# Uno_Base_Shield.net
KiCad netlist of a schematic drawn in EAGLE
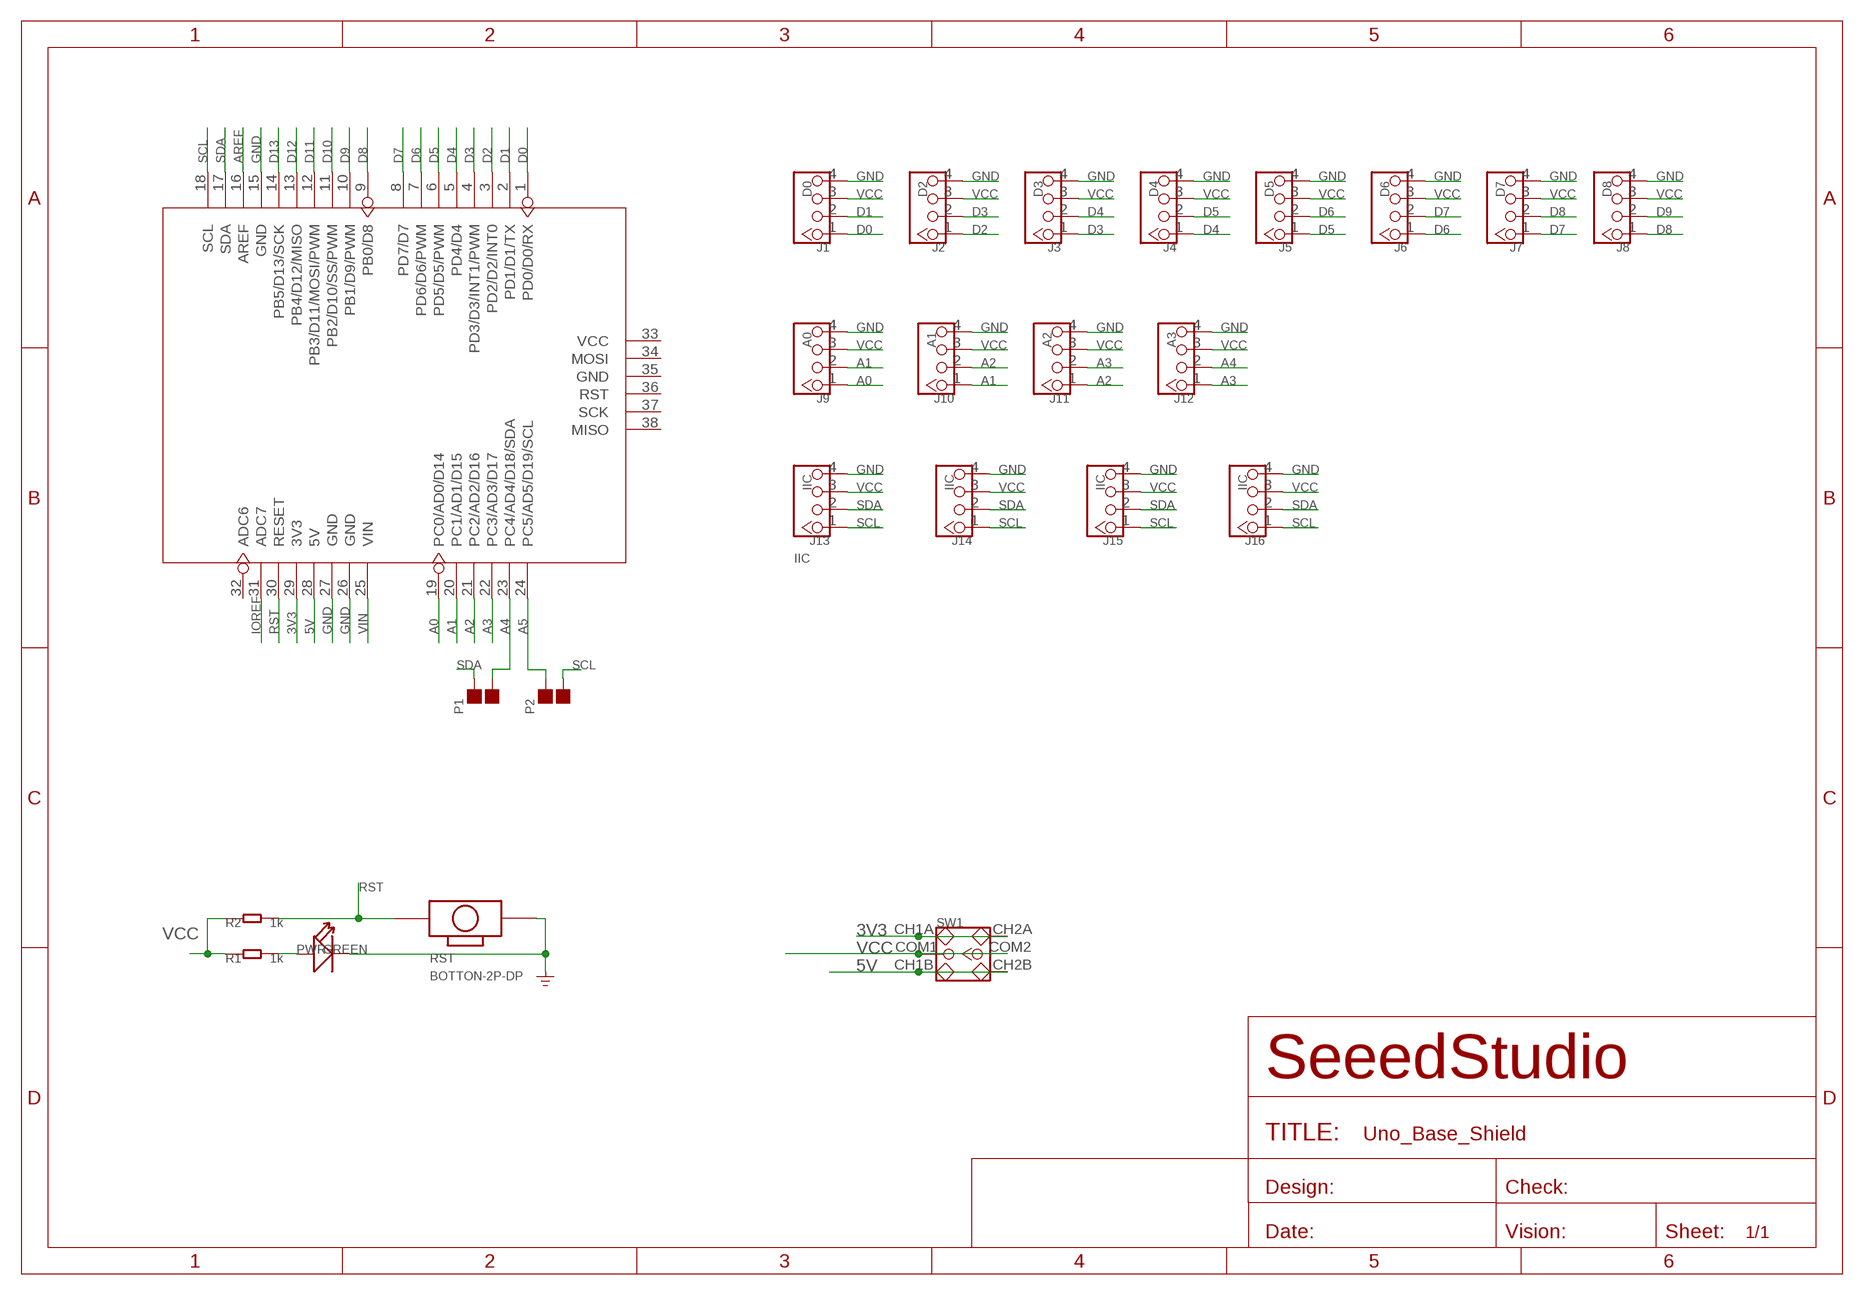
[diagram p0: schematic, sheet 1]

(export (version "E")
  (design (tool "Eeschema 10.0.6"))
  (components
    (comp (ref "J1")
      (value "D0")
      (footprint "eagle-import:4P-2.0")
      (libsource (lib "eagle-import") (part "TWIG-4P-2.0-2.0"))
    )
    (comp (ref "J2")
      (value "D2")
      (footprint "eagle-import:4P-2.0")
      (libsource (lib "eagle-import") (part "TWIG-4P-2.0-2.0"))
    )
    (comp (ref "J3")
      (value "D3")
      (footprint "eagle-import:4P-2.0")
      (libsource (lib "eagle-import") (part "TWIG-4P-2.0-2.0"))
    )
    (comp (ref "J4")
      (value "D4")
      (footprint "eagle-import:4P-2.0")
      (libsource (lib "eagle-import") (part "TWIG-4P-2.0-2.0"))
    )
    (comp (ref "J5")
      (value "D5")
      (footprint "eagle-import:4P-2.0")
      (libsource (lib "eagle-import") (part "TWIG-4P-2.0-2.0"))
    )
    (comp (ref "J6")
      (value "D6")
      (footprint "eagle-import:4P-2.0")
      (libsource (lib "eagle-import") (part "TWIG-4P-2.0-2.0"))
    )
    (comp (ref "J7")
      (value "D7")
      (footprint "eagle-import:4P-2.0")
      (libsource (lib "eagle-import") (part "TWIG-4P-2.0-2.0"))
    )
    (comp (ref "J8")
      (value "D8")
      (footprint "eagle-import:4P-2.0")
      (libsource (lib "eagle-import") (part "TWIG-4P-2.0-2.0"))
    )
    (comp (ref "J9")
      (value "A0")
      (footprint "eagle-import:4P-2.0-90D")
      (libsource (lib "eagle-import") (part "TWIG-4P-2.0'90D'"))
    )
    (comp (ref "J10")
      (value "A1")
      (footprint "eagle-import:4P-2.0-90D")
      (libsource (lib "eagle-import") (part "TWIG-4P-2.0'90D'"))
    )
    (comp (ref "J11")
      (value "A2")
      (footprint "eagle-import:4P-2.0-90D")
      (libsource (lib "eagle-import") (part "TWIG-4P-2.0'90D'"))
    )
    (comp (ref "J12")
      (value "A3")
      (footprint "eagle-import:4P-2.0-90D")
      (libsource (lib "eagle-import") (part "TWIG-4P-2.0'90D'"))
    )
    (comp (ref "J13")
      (value "IIC")
      (footprint "eagle-import:4P-2.0")
      (libsource (lib "eagle-import") (part "TWIG-4P-2.0-2.0"))
    )
    (comp (ref "J14")
      (value "IIC")
      (footprint "eagle-import:4P-2.0")
      (libsource (lib "eagle-import") (part "TWIG-4P-2.0-2.0"))
    )
    (comp (ref "J15")
      (value "IIC")
      (footprint "eagle-import:4P-2.0")
      (libsource (lib "eagle-import") (part "TWIG-4P-2.0-2.0"))
    )
    (comp (ref "J16")
      (value "IIC")
      (footprint "eagle-import:4P-2.0")
      (libsource (lib "eagle-import") (part "TWIG-4P-2.0-2.0"))
    )
    (comp (ref "P1")
      (value "DNP")
      (footprint "eagle-import:2P-SMD-1.78X1.27")
      (libsource (lib "eagle-import") (part "PAD-JUMPER-2P"))
    )
    (comp (ref "P2")
      (value "DNP")
      (footprint "eagle-import:2P-SMD-1.78X1.27")
      (libsource (lib "eagle-import") (part "PAD-JUMPER-2P"))
    )
    (comp (ref "PWR")
      (value "GREEN")
      (footprint "eagle-import:LED-2P-2.54-3MM")
      (libsource (lib "eagle-import") (part "LED-3MM"))
    )
    (comp (ref "R1")
      (value "1k")
      (footprint "eagle-import:R0603")
      (libsource (lib "eagle-import") (part "R-0603"))
    )
    (comp (ref "R2")
      (value "1k")
      (footprint "eagle-import:R0603")
      (libsource (lib "eagle-import") (part "R-0603"))
    )
    (comp (ref "RST")
      (value "BOTTON-2P-DP")
      (footprint "eagle-import:2P-7.62X3.56-90D")
      (libsource (lib "eagle-import") (part "BOTTON-2P-90"))
    )
    (comp (ref "SW1")
      (value "SWITCH-2CH-6P'90D'")
      (footprint "eagle-import:6P-2CH-2.5-9.1X3.5X3.2H-90D")
      (libsource (lib "eagle-import") (part "SWITCH-2CH-6P'90D'"))
    )
    (comp (ref "U2")
      (value "DIP Long Blue Female Header")
      (footprint "eagle-import:ARDUINO-38P")
      (libsource (lib "eagle-import") (part "ARDUINO-38P"))
    )
  )
  (nets
    (net (code "1") (name "/3V3") (class "Default")
      (node (ref "SW1") (pin "CH1A") (pinfunction "CH1A_CH1A") (pintype "bidirectional"))
      (node (ref "SW1") (pin "CH2A") (pinfunction "CH2A_CH2A") (pintype "bidirectional"))
      (node (ref "U2") (pin "29") (pinfunction "3V3_29") (pintype "bidirectional"))
    )
    (net (code "2") (name "/5V") (class "Default")
      (node (ref "SW1") (pin "CH1B") (pinfunction "CH1B_CH1B") (pintype "bidirectional"))
      (node (ref "SW1") (pin "CH2B") (pinfunction "CH2B_CH2B") (pintype "bidirectional"))
      (node (ref "U2") (pin "28") (pinfunction "5V_28") (pintype "bidirectional"))
    )
    (net (code "3") (name "/A0") (class "Default")
      (node (ref "J9") (pin "1") (pinfunction "1_1") (pintype "bidirectional"))
      (node (ref "U2") (pin "19") (pinfunction "PC0/AD0/D14_19") (pintype "bidirectional"))
    )
    (net (code "4") (name "/A1") (class "Default")
      (node (ref "J10") (pin "1") (pinfunction "1_1") (pintype "bidirectional"))
      (node (ref "J9") (pin "2") (pinfunction "2_2") (pintype "bidirectional"))
      (node (ref "U2") (pin "20") (pinfunction "PC1/AD1/D15_20") (pintype "bidirectional"))
    )
    (net (code "5") (name "/A2") (class "Default")
      (node (ref "J10") (pin "2") (pinfunction "2_2") (pintype "bidirectional"))
      (node (ref "J11") (pin "1") (pinfunction "1_1") (pintype "bidirectional"))
      (node (ref "U2") (pin "21") (pinfunction "PC2/AD2/D16_21") (pintype "bidirectional"))
    )
    (net (code "6") (name "/A3") (class "Default")
      (node (ref "J11") (pin "2") (pinfunction "2_2") (pintype "bidirectional"))
      (node (ref "J12") (pin "1") (pinfunction "1_1") (pintype "bidirectional"))
      (node (ref "U2") (pin "22") (pinfunction "PC3/AD3/D17_22") (pintype "bidirectional"))
    )
    (net (code "7") (name "/A4") (class "Default")
      (node (ref "J12") (pin "2") (pinfunction "2_2") (pintype "bidirectional"))
      (node (ref "P1") (pin "1") (pinfunction "1_1") (pintype "bidirectional"))
      (node (ref "U2") (pin "23") (pinfunction "PC4/AD4/D18/SDA_23") (pintype "bidirectional"))
    )
    (net (code "8") (name "/A5") (class "Default")
      (node (ref "P2") (pin "2") (pinfunction "2_2") (pintype "bidirectional"))
      (node (ref "U2") (pin "24") (pinfunction "PC5/AD5/D19/SCL_24") (pintype "bidirectional"))
    )
    (net (code "9") (name "/AREF") (class "Default")
      (node (ref "U2") (pin "16") (pinfunction "AREF_16") (pintype "bidirectional"))
    )
    (net (code "10") (name "/D0") (class "Default")
      (node (ref "J1") (pin "1") (pinfunction "1_1") (pintype "bidirectional"))
      (node (ref "U2") (pin "1") (pinfunction "PD0/D0/RX_1") (pintype "bidirectional"))
    )
    (net (code "11") (name "/D1") (class "Default")
      (node (ref "J1") (pin "2") (pinfunction "2_2") (pintype "bidirectional"))
      (node (ref "U2") (pin "2") (pinfunction "PD1/D1/TX_2") (pintype "bidirectional"))
    )
    (net (code "12") (name "/D2") (class "Default")
      (node (ref "J2") (pin "1") (pinfunction "1_1") (pintype "bidirectional"))
      (node (ref "U2") (pin "3") (pinfunction "PD2/D2/INT0_3") (pintype "bidirectional"))
    )
    (net (code "13") (name "/D3") (class "Default")
      (node (ref "J2") (pin "2") (pinfunction "2_2") (pintype "bidirectional"))
      (node (ref "J3") (pin "1") (pinfunction "1_1") (pintype "bidirectional"))
      (node (ref "U2") (pin "4") (pinfunction "PD3/D3/INT1/PWM_4") (pintype "bidirectional"))
    )
    (net (code "14") (name "/D4") (class "Default")
      (node (ref "J3") (pin "2") (pinfunction "2_2") (pintype "bidirectional"))
      (node (ref "J4") (pin "1") (pinfunction "1_1") (pintype "bidirectional"))
      (node (ref "U2") (pin "5") (pinfunction "PD4/D4_5") (pintype "bidirectional"))
    )
    (net (code "15") (name "/D5") (class "Default")
      (node (ref "J4") (pin "2") (pinfunction "2_2") (pintype "bidirectional"))
      (node (ref "J5") (pin "1") (pinfunction "1_1") (pintype "bidirectional"))
      (node (ref "U2") (pin "6") (pinfunction "PD5/D5/PWM_6") (pintype "bidirectional"))
    )
    (net (code "16") (name "/D6") (class "Default")
      (node (ref "J5") (pin "2") (pinfunction "2_2") (pintype "bidirectional"))
      (node (ref "J6") (pin "1") (pinfunction "1_1") (pintype "bidirectional"))
      (node (ref "U2") (pin "7") (pinfunction "PD6/D6/PWM_7") (pintype "bidirectional"))
    )
    (net (code "17") (name "/D7") (class "Default")
      (node (ref "J6") (pin "2") (pinfunction "2_2") (pintype "bidirectional"))
      (node (ref "J7") (pin "1") (pinfunction "1_1") (pintype "bidirectional"))
      (node (ref "U2") (pin "8") (pinfunction "PD7/D7_8") (pintype "bidirectional"))
    )
    (net (code "18") (name "/D8") (class "Default")
      (node (ref "J7") (pin "2") (pinfunction "2_2") (pintype "bidirectional"))
      (node (ref "J8") (pin "1") (pinfunction "1_1") (pintype "bidirectional"))
      (node (ref "U2") (pin "9") (pinfunction "PB0/D8_9") (pintype "bidirectional"))
    )
    (net (code "19") (name "/D9") (class "Default")
      (node (ref "J8") (pin "2") (pinfunction "2_2") (pintype "bidirectional"))
      (node (ref "U2") (pin "10") (pinfunction "PB1/D9/PWM_10") (pintype "bidirectional"))
    )
    (net (code "20") (name "/D10") (class "Default")
      (node (ref "U2") (pin "11") (pinfunction "PB2/D10/SS/PWM_11") (pintype "bidirectional"))
    )
    (net (code "21") (name "/D11") (class "Default")
      (node (ref "U2") (pin "12") (pinfunction "PB3/D11/MOSI/PWM_12") (pintype "bidirectional"))
    )
    (net (code "22") (name "/D12") (class "Default")
      (node (ref "U2") (pin "13") (pinfunction "PB4/D12/MISO_13") (pintype "bidirectional"))
    )
    (net (code "23") (name "/D13") (class "Default")
      (node (ref "U2") (pin "14") (pinfunction "PB5/D13/SCK_14") (pintype "bidirectional"))
    )
    (net (code "24") (name "/IOREF") (class "Default")
      (node (ref "U2") (pin "31") (pinfunction "ADC7_31") (pintype "bidirectional"))
    )
    (net (code "25") (name "/RST") (class "Default")
      (node (ref "R2") (pin "2") (pinfunction "2_2") (pintype "passive"))
      (node (ref "RST") (pin "P$1") (pinfunction "1_P$1") (pintype "bidirectional"))
      (node (ref "U2") (pin "30") (pinfunction "RESET_30") (pintype "bidirectional"))
    )
    (net (code "26") (name "/SCL") (class "Default")
      (node (ref "J13") (pin "1") (pinfunction "1_1") (pintype "bidirectional"))
      (node (ref "J14") (pin "1") (pinfunction "1_1") (pintype "bidirectional"))
      (node (ref "J15") (pin "1") (pinfunction "1_1") (pintype "bidirectional"))
      (node (ref "J16") (pin "1") (pinfunction "1_1") (pintype "bidirectional"))
      (node (ref "P2") (pin "1") (pinfunction "1_1") (pintype "bidirectional"))
      (node (ref "U2") (pin "18") (pinfunction "SCL_18") (pintype "bidirectional"))
    )
    (net (code "27") (name "/SDA") (class "Default")
      (node (ref "J13") (pin "2") (pinfunction "2_2") (pintype "bidirectional"))
      (node (ref "J14") (pin "2") (pinfunction "2_2") (pintype "bidirectional"))
      (node (ref "J15") (pin "2") (pinfunction "2_2") (pintype "bidirectional"))
      (node (ref "J16") (pin "2") (pinfunction "2_2") (pintype "bidirectional"))
      (node (ref "P1") (pin "2") (pinfunction "2_2") (pintype "bidirectional"))
      (node (ref "U2") (pin "17") (pinfunction "SDA_17") (pintype "bidirectional"))
    )
    (net (code "28") (name "/VCC") (class "Default")
      (node (ref "J1") (pin "3") (pinfunction "3_3") (pintype "bidirectional"))
      (node (ref "J10") (pin "3") (pinfunction "3_3") (pintype "bidirectional"))
      (node (ref "J11") (pin "3") (pinfunction "3_3") (pintype "bidirectional"))
      (node (ref "J12") (pin "3") (pinfunction "3_3") (pintype "bidirectional"))
      (node (ref "J13") (pin "3") (pinfunction "3_3") (pintype "bidirectional"))
      (node (ref "J14") (pin "3") (pinfunction "3_3") (pintype "bidirectional"))
      (node (ref "J15") (pin "3") (pinfunction "3_3") (pintype "bidirectional"))
      (node (ref "J16") (pin "3") (pinfunction "3_3") (pintype "bidirectional"))
      (node (ref "J2") (pin "3") (pinfunction "3_3") (pintype "bidirectional"))
      (node (ref "J3") (pin "3") (pinfunction "3_3") (pintype "bidirectional"))
      (node (ref "J4") (pin "3") (pinfunction "3_3") (pintype "bidirectional"))
      (node (ref "J5") (pin "3") (pinfunction "3_3") (pintype "bidirectional"))
      (node (ref "J6") (pin "3") (pinfunction "3_3") (pintype "bidirectional"))
      (node (ref "J7") (pin "3") (pinfunction "3_3") (pintype "bidirectional"))
      (node (ref "J8") (pin "3") (pinfunction "3_3") (pintype "bidirectional"))
      (node (ref "J9") (pin "3") (pinfunction "3_3") (pintype "bidirectional"))
      (node (ref "R1") (pin "1") (pinfunction "1_1") (pintype "passive"))
      (node (ref "R2") (pin "1") (pinfunction "1_1") (pintype "passive"))
      (node (ref "SW1") (pin "COM1") (pinfunction "COM1_COM1") (pintype "bidirectional"))
      (node (ref "SW1") (pin "COM2") (pinfunction "COM2_COM2") (pintype "bidirectional"))
    )
    (net (code "29") (name "/VIN") (class "Default")
      (node (ref "U2") (pin "25") (pinfunction "VIN_25") (pintype "bidirectional"))
    )
    (net (code "30") (name "GND_POWER") (class "Default")
      (node (ref "J1") (pin "4") (pinfunction "4_4") (pintype "bidirectional"))
      (node (ref "J10") (pin "4") (pinfunction "4_4") (pintype "bidirectional"))
      (node (ref "J11") (pin "4") (pinfunction "4_4") (pintype "bidirectional"))
      (node (ref "J12") (pin "4") (pinfunction "4_4") (pintype "bidirectional"))
      (node (ref "J13") (pin "4") (pinfunction "4_4") (pintype "bidirectional"))
      (node (ref "J14") (pin "4") (pinfunction "4_4") (pintype "bidirectional"))
      (node (ref "J15") (pin "4") (pinfunction "4_4") (pintype "bidirectional"))
      (node (ref "J16") (pin "4") (pinfunction "4_4") (pintype "bidirectional"))
      (node (ref "J2") (pin "4") (pinfunction "4_4") (pintype "bidirectional"))
      (node (ref "J3") (pin "4") (pinfunction "4_4") (pintype "bidirectional"))
      (node (ref "J4") (pin "4") (pinfunction "4_4") (pintype "bidirectional"))
      (node (ref "J5") (pin "4") (pinfunction "4_4") (pintype "bidirectional"))
      (node (ref "J6") (pin "4") (pinfunction "4_4") (pintype "bidirectional"))
      (node (ref "J7") (pin "4") (pinfunction "4_4") (pintype "bidirectional"))
      (node (ref "J8") (pin "4") (pinfunction "4_4") (pintype "bidirectional"))
      (node (ref "J9") (pin "4") (pinfunction "4_4") (pintype "bidirectional"))
      (node (ref "PWR") (pin "K") (pinfunction "-_K") (pintype "passive"))
      (node (ref "RST") (pin "P$2") (pinfunction "2_P$2") (pintype "bidirectional"))
      (node (ref "U2") (pin "15") (pinfunction "GND_15") (pintype "bidirectional"))
      (node (ref "U2") (pin "26") (pinfunction "GND_26") (pintype "bidirectional"))
      (node (ref "U2") (pin "27") (pinfunction "GND_27") (pintype "bidirectional"))
    )
    (net (code "31") (name "Net-(PWR-+)") (class "Default")
      (node (ref "PWR") (pin "A") (pinfunction "+_A") (pintype "passive"))
      (node (ref "R1") (pin "2") (pinfunction "2_2") (pintype "passive"))
    )
    (net (code "32") (name "unconnected-(U2-ADC6-Pad32)") (class "Default")
      (node (ref "U2") (pin "32") (pinfunction "ADC6_32") (pintype "bidirectional"))
    )
    (net (code "33") (name "unconnected-(U2-GND-Pad35)") (class "Default")
      (node (ref "U2") (pin "35") (pinfunction "GND_35") (pintype "bidirectional"))
    )
    (net (code "34") (name "unconnected-(U2-MISO-Pad38)") (class "Default")
      (node (ref "U2") (pin "38") (pinfunction "MISO_38") (pintype "bidirectional"))
    )
    (net (code "35") (name "unconnected-(U2-MOSI-Pad34)") (class "Default")
      (node (ref "U2") (pin "34") (pinfunction "MOSI_34") (pintype "bidirectional"))
    )
    (net (code "36") (name "unconnected-(U2-RST-Pad36)") (class "Default")
      (node (ref "U2") (pin "36") (pinfunction "RST_36") (pintype "bidirectional"))
    )
    (net (code "37") (name "unconnected-(U2-SCK-Pad37)") (class "Default")
      (node (ref "U2") (pin "37") (pinfunction "SCK_37") (pintype "bidirectional"))
    )
    (net (code "38") (name "unconnected-(U2-VCC-Pad33)") (class "Default")
      (node (ref "U2") (pin "33") (pinfunction "VCC_33") (pintype "bidirectional"))
    )
  )
)
